# address_decoding_rw_8bytes.net
KiCad netlist of a schematic drawn in EAGLE
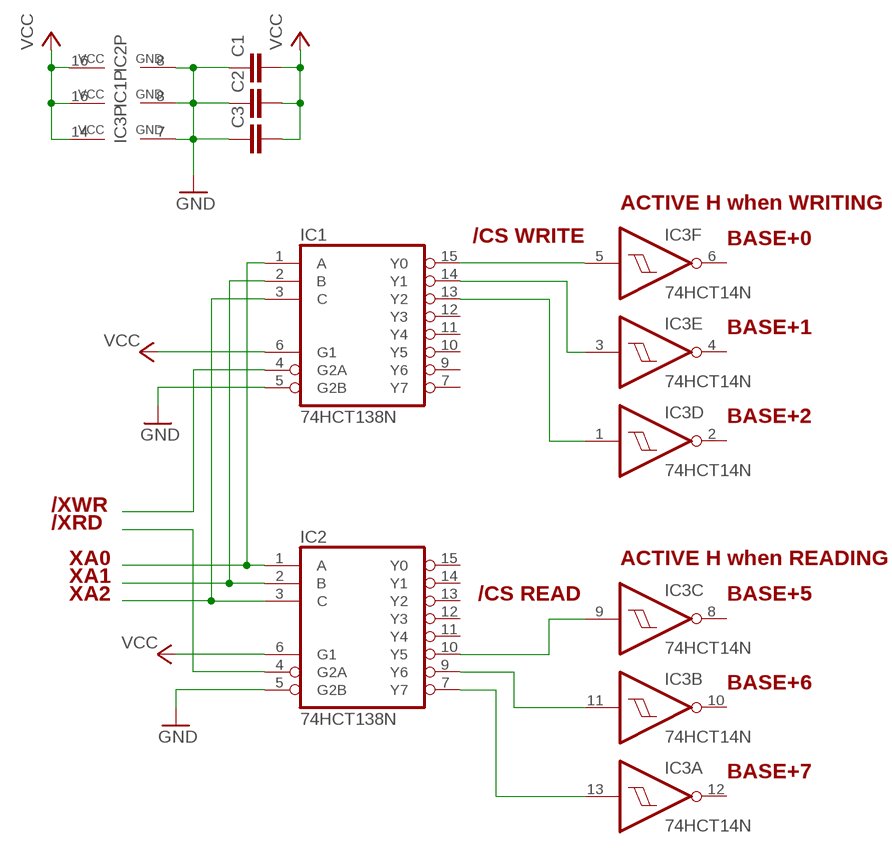
[diagram p0: schematic, sheet 1]

(export (version "E")
  (design (tool "Eeschema 10.0.6"))
  (components
    (comp (ref "C1")
      (value "C-EU025-024X044")
      (footprint "eagle-import:C025-024X044")
      (libsource (lib "eagle-import") (part "C-EU025-024X044"))
    )
    (comp (ref "C2")
      (value "C-EU025-024X044")
      (footprint "eagle-import:C025-024X044")
      (libsource (lib "eagle-import") (part "C-EU025-024X044"))
    )
    (comp (ref "C3")
      (value "C-EU025-024X044")
      (footprint "eagle-import:C025-024X044")
      (libsource (lib "eagle-import") (part "C-EU025-024X044"))
    )
    (comp (ref "IC1")
      (value "74HCT138N")
      (footprint "eagle-import:DIL16")
      (libsource (lib "eagle-import") (part "74138NHCT"))
    )
    (comp (ref "IC2")
      (value "74HCT138N")
      (footprint "eagle-import:DIL16")
      (libsource (lib "eagle-import") (part "74138NHCT"))
    )
    (comp (ref "IC3")
      (value "74HCT14N")
      (footprint "eagle-import:DIL14")
      (libsource (lib "eagle-import") (part "7414NHCT"))
    )
  )
  (nets
    (net (code "1") (name "GND") (class "Default")
      (node (ref "C1") (pin "1") (pinfunction "1_1") (pintype "passive"))
      (node (ref "C2") (pin "1") (pinfunction "1_1") (pintype "passive"))
      (node (ref "C3") (pin "1") (pinfunction "1_1") (pintype "passive"))
      (node (ref "IC1") (pin "5") (pinfunction "G2B_5") (pintype "input"))
      (node (ref "IC1") (pin "8") (pinfunction "GND_8") (pintype "power_in"))
      (node (ref "IC2") (pin "5") (pinfunction "G2B_5") (pintype "input"))
      (node (ref "IC2") (pin "8") (pinfunction "GND_8") (pintype "power_in"))
      (node (ref "IC3") (pin "7") (pinfunction "GND_7") (pintype "power_in"))
    )
    (net (code "2") (name "Net-(IC1A-A)") (class "Default")
      (node (ref "IC1") (pin "1") (pinfunction "A_1") (pintype "input"))
      (node (ref "IC2") (pin "1") (pinfunction "A_1") (pintype "input"))
    )
    (net (code "3") (name "Net-(IC1A-B)") (class "Default")
      (node (ref "IC1") (pin "2") (pinfunction "B_2") (pintype "input"))
      (node (ref "IC2") (pin "2") (pinfunction "B_2") (pintype "input"))
    )
    (net (code "4") (name "Net-(IC1A-C)") (class "Default")
      (node (ref "IC1") (pin "3") (pinfunction "C_3") (pintype "input"))
      (node (ref "IC2") (pin "3") (pinfunction "C_3") (pintype "input"))
    )
    (net (code "5") (name "Net-(IC1A-Y0)") (class "Default")
      (node (ref "IC1") (pin "15") (pinfunction "Y0_15") (pintype "output"))
      (node (ref "IC3") (pin "5") (pinfunction "I_5") (pintype "input"))
    )
    (net (code "6") (name "Net-(IC1A-Y1)") (class "Default")
      (node (ref "IC1") (pin "14") (pinfunction "Y1_14") (pintype "output"))
      (node (ref "IC3") (pin "3") (pinfunction "I_3") (pintype "input"))
    )
    (net (code "7") (name "Net-(IC1A-Y2)") (class "Default")
      (node (ref "IC1") (pin "13") (pinfunction "Y2_13") (pintype "output"))
      (node (ref "IC3") (pin "1") (pinfunction "I_1") (pintype "input"))
    )
    (net (code "8") (name "Net-(IC2A-Y5)") (class "Default")
      (node (ref "IC2") (pin "10") (pinfunction "Y5_10") (pintype "output"))
      (node (ref "IC3") (pin "9") (pinfunction "I_9") (pintype "input"))
    )
    (net (code "9") (name "Net-(IC2A-Y6)") (class "Default")
      (node (ref "IC2") (pin "9") (pinfunction "Y6_9") (pintype "output"))
      (node (ref "IC3") (pin "11") (pinfunction "I_11") (pintype "input"))
    )
    (net (code "10") (name "Net-(IC2A-Y7)") (class "Default")
      (node (ref "IC2") (pin "7") (pinfunction "Y7_7") (pintype "output"))
      (node (ref "IC3") (pin "13") (pinfunction "I_13") (pintype "input"))
    )
    (net (code "11") (name "VCC") (class "Default")
      (node (ref "C1") (pin "2") (pinfunction "2_2") (pintype "passive"))
      (node (ref "C2") (pin "2") (pinfunction "2_2") (pintype "passive"))
      (node (ref "C3") (pin "2") (pinfunction "2_2") (pintype "passive"))
      (node (ref "IC1") (pin "16") (pinfunction "VCC_16") (pintype "power_in"))
      (node (ref "IC1") (pin "6") (pinfunction "G1_6") (pintype "input"))
      (node (ref "IC2") (pin "16") (pinfunction "VCC_16") (pintype "power_in"))
      (node (ref "IC2") (pin "6") (pinfunction "G1_6") (pintype "input"))
      (node (ref "IC3") (pin "14") (pinfunction "VCC_14") (pintype "power_in"))
    )
    (net (code "12") (name "unconnected-(IC1A-G2A-Pad4)") (class "Default")
      (node (ref "IC1") (pin "4") (pinfunction "G2A_4") (pintype "input"))
    )
    (net (code "13") (name "unconnected-(IC1A-Y3-Pad12)") (class "Default")
      (node (ref "IC1") (pin "12") (pinfunction "Y3_12") (pintype "output"))
    )
    (net (code "14") (name "unconnected-(IC1A-Y4-Pad11)") (class "Default")
      (node (ref "IC1") (pin "11") (pinfunction "Y4_11") (pintype "output"))
    )
    (net (code "15") (name "unconnected-(IC1A-Y5-Pad10)") (class "Default")
      (node (ref "IC1") (pin "10") (pinfunction "Y5_10") (pintype "output"))
    )
    (net (code "16") (name "unconnected-(IC1A-Y6-Pad9)") (class "Default")
      (node (ref "IC1") (pin "9") (pinfunction "Y6_9") (pintype "output"))
    )
    (net (code "17") (name "unconnected-(IC1A-Y7-Pad7)") (class "Default")
      (node (ref "IC1") (pin "7") (pinfunction "Y7_7") (pintype "output"))
    )
    (net (code "18") (name "unconnected-(IC2A-G2A-Pad4)") (class "Default")
      (node (ref "IC2") (pin "4") (pinfunction "G2A_4") (pintype "input"))
    )
    (net (code "19") (name "unconnected-(IC2A-Y0-Pad15)") (class "Default")
      (node (ref "IC2") (pin "15") (pinfunction "Y0_15") (pintype "output"))
    )
    (net (code "20") (name "unconnected-(IC2A-Y1-Pad14)") (class "Default")
      (node (ref "IC2") (pin "14") (pinfunction "Y1_14") (pintype "output"))
    )
    (net (code "21") (name "unconnected-(IC2A-Y2-Pad13)") (class "Default")
      (node (ref "IC2") (pin "13") (pinfunction "Y2_13") (pintype "output"))
    )
    (net (code "22") (name "unconnected-(IC2A-Y3-Pad12)") (class "Default")
      (node (ref "IC2") (pin "12") (pinfunction "Y3_12") (pintype "output"))
    )
    (net (code "23") (name "unconnected-(IC2A-Y4-Pad11)") (class "Default")
      (node (ref "IC2") (pin "11") (pinfunction "Y4_11") (pintype "output"))
    )
    (net (code "24") (name "unconnected-(IC3A-O-Pad12)") (class "Default")
      (node (ref "IC3") (pin "12") (pinfunction "O_12") (pintype "output"))
    )
    (net (code "25") (name "unconnected-(IC3B-O-Pad10)") (class "Default")
      (node (ref "IC3") (pin "10") (pinfunction "O_10") (pintype "output"))
    )
    (net (code "26") (name "unconnected-(IC3C-O-Pad8)") (class "Default")
      (node (ref "IC3") (pin "8") (pinfunction "O_8") (pintype "output"))
    )
    (net (code "27") (name "unconnected-(IC3D-O-Pad2)") (class "Default")
      (node (ref "IC3") (pin "2") (pinfunction "O_2") (pintype "output"))
    )
    (net (code "28") (name "unconnected-(IC3E-O-Pad4)") (class "Default")
      (node (ref "IC3") (pin "4") (pinfunction "O_4") (pintype "output"))
    )
    (net (code "29") (name "unconnected-(IC3F-O-Pad6)") (class "Default")
      (node (ref "IC3") (pin "6") (pinfunction "O_6") (pintype "output"))
    )
  )
)
